# 09_-_mPCIE.net
KiCad netlist of a schematic drawn in Altium Designer
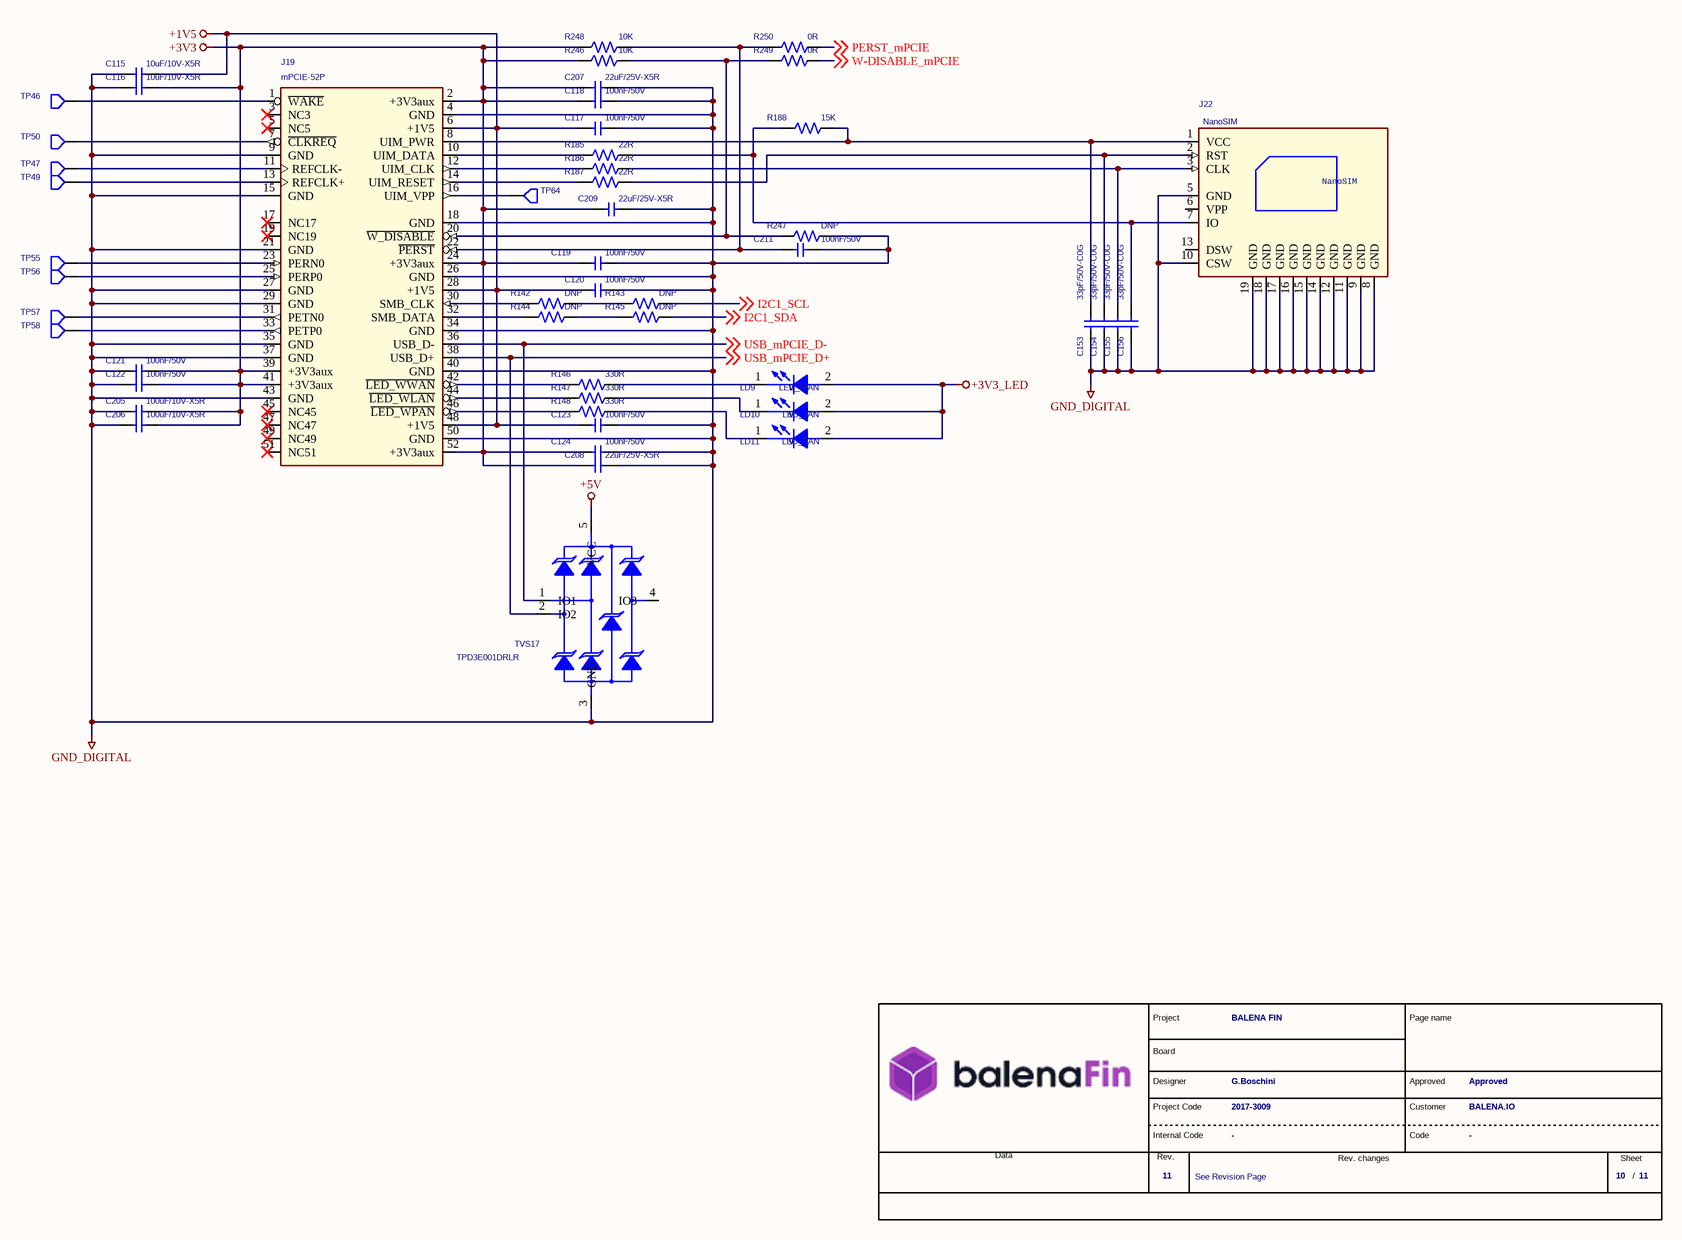
[diagram p0: 09 - mPCIE.SchDoc]

(export (version "E")
  (design (tool "Eeschema 10.0.6"))
  (components
    (comp (ref "C115")
      (value "10uF/10V-X5R")
      (footprint "CS-C-0603")
      (description "CHIP CAP.CER. 10uF 10V 10% X5R 0603")
      (fields (field (name "MPN") "Generic"))
      (libsource (lib "*") (part "CS-C-0603-10u/10V-X5R"))
    )
    (comp (ref "C116")
      (value "10uF/10V-X5R")
      (footprint "CS-C-0603")
      (description "CHIP CAP.CER. 10uF 10V 10% X5R 0603")
      (fields (field (name "MPN") "Generic"))
      (libsource (lib "*") (part "CS-C-0603-10u/10V-X5R"))
    )
    (comp (ref "C117")
      (value "100nF/50V")
      (footprint "CS-C-0402")
      (description "CHIP CAP.CER. 100nF 16V 10% X7R 0402")
      (fields (field (name "MPN") "Generic"))
      (libsource (lib "*") (part "CS-C-0402-100n/16V"))
    )
    (comp (ref "C118")
      (value "100nF/50V")
      (footprint "CS-C-0402")
      (description "CHIP CAP.CER. 100nF 16V 10% X7R 0402")
      (fields (field (name "MPN") "Generic"))
      (libsource (lib "*") (part "CS-C-0402-100n/16V"))
    )
    (comp (ref "C119")
      (value "100nF/50V")
      (footprint "CS-C-0402")
      (description "CHIP CAP.CER. 100nF 16V 10% X7R 0402")
      (fields (field (name "MPN") "Generic"))
      (libsource (lib "*") (part "CS-C-0402-100n/16V"))
    )
    (comp (ref "C120")
      (value "100nF/50V")
      (footprint "CS-C-0402")
      (description "CHIP CAP.CER. 100nF 16V 10% X7R 0402")
      (fields (field (name "MPN") "Generic"))
      (libsource (lib "*") (part "CS-C-0402-100n/16V"))
    )
    (comp (ref "C121")
      (value "100nF/50V")
      (footprint "CS-C-0402")
      (description "CHIP CAP.CER. 100nF 16V 10% X7R 0402")
      (fields (field (name "MPN") "Generic"))
      (libsource (lib "*") (part "CS-C-0402-100n/16V"))
    )
    (comp (ref "C122")
      (value "100nF/50V")
      (footprint "CS-C-0402")
      (description "CHIP CAP.CER. 100nF 16V 10% X7R 0402")
      (fields (field (name "MPN") "Generic"))
      (libsource (lib "*") (part "CS-C-0402-100n/16V"))
    )
    (comp (ref "C123")
      (value "100nF/50V")
      (footprint "CS-C-0402")
      (description "CHIP CAP.CER. 100nF 16V 10% X7R 0402")
      (fields (field (name "MPN") "Generic"))
      (libsource (lib "*") (part "CS-C-0402-100n/16V"))
    )
    (comp (ref "C124")
      (value "100nF/50V")
      (footprint "CS-C-0402")
      (description "CHIP CAP.CER. 100nF 16V 10% X7R 0402")
      (fields (field (name "MPN") "Generic"))
      (libsource (lib "*") (part "CS-C-0402-100n/16V"))
    )
    (comp (ref "C153")
      (value "33pF/50V-C0G")
      (footprint "CS-C-0402")
      (description "CHIP CAP.CER. 33pF 50V 5% C0G 0402")
      (fields (field (name "MPN") "Generic"))
      (libsource (lib "*") (part "CS-C-0402-33p/50V-C0G"))
    )
    (comp (ref "C154")
      (value "33pF/50V-C0G")
      (footprint "CS-C-0402")
      (description "CHIP CAP.CER. 33pF 50V 5% C0G 0402")
      (fields (field (name "MPN") "Generic"))
      (libsource (lib "*") (part "CS-C-0402-33p/50V-C0G"))
    )
    (comp (ref "C155")
      (value "33pF/50V-C0G")
      (footprint "CS-C-0402")
      (description "CHIP CAP.CER. 33pF 50V 5% C0G 0402")
      (fields (field (name "MPN") "Generic"))
      (libsource (lib "*") (part "CS-C-0402-33p/50V-C0G"))
    )
    (comp (ref "C156")
      (value "33pF/50V-C0G")
      (footprint "CS-C-0402")
      (description "CHIP CAP.CER. 33pF 50V 5% C0G 0402")
      (fields (field (name "MPN") "Generic"))
      (libsource (lib "*") (part "CS-C-0402-33p/50V-C0G"))
    )
    (comp (ref "C205")
      (value "100uF/10V-X5R")
      (footprint "CS-C-1210")
      (description "CHIP CAP.CER. 100UF 10V 20% X5R 1210")
      (fields (field (name "MPN") "Generic"))
      (libsource (lib "*") (part "CS-C-1210-100u/10V-X5R"))
    )
    (comp (ref "C206")
      (value "100uF/10V-X5R")
      (footprint "CS-C-1210")
      (description "CHIP CAP.CER. 100UF 10V 20% X5R 1210")
      (fields (field (name "MPN") "Generic"))
      (libsource (lib "*") (part "CS-C-1210-100u/10V-X5R"))
    )
    (comp (ref "C207")
      (value "22uF/25V-X5R")
      (footprint "CS-C-1206")
      (description "CHIP CAP.CER. 22uF 25V 10% X5R 1206")
      (fields (field (name "MPN") "Generic"))
      (libsource (lib "*") (part "CS-C-1206-22u/25V-X5R"))
    )
    (comp (ref "C208")
      (value "22uF/25V-X5R")
      (footprint "CS-C-1206")
      (description "CHIP CAP.CER. 22uF 25V 10% X5R 1206")
      (fields (field (name "MPN") "Generic"))
      (libsource (lib "*") (part "CS-C-1206-22u/25V-X5R"))
    )
    (comp (ref "C209")
      (value "22uF/25V-X5R")
      (footprint "CS-C-1206")
      (description "CHIP CAP.CER. 22uF 25V 10% X5R 1206")
      (fields (field (name "MPN") "Generic"))
      (libsource (lib "*") (part "CS-C-1206-22u/25V-X5R"))
    )
    (comp (ref "C211")
      (value "100nF/50V")
      (footprint "CS-C-0402")
      (description "CHIP CAP.CER. 100nF 16V 10% X7R 0402")
      (fields (field (name "MPN") "Generic"))
      (libsource (lib "*") (part "CS-C-0402-100n/16V"))
    )
    (comp (ref "J19")
      (value "mPCIE-52P")
      (footprint "J-26X2-0080-FOS-2041119")
      (description "CONN PCI EXP MINI FEMALE 52POS")
      (fields (field (name "MPN") "2041119-1"))
      (libsource (lib "*") (part "mPCIE - J-26X2-0080-FOS-2041119"))
    )
    (comp (ref "J22")
      (value "NanoSIM")
      (footprint "J-NANOSIM-SF72S006VBA")
      (description "CONN NANO SIM CARD PUSH-PUSH")
      (fields (field (name "MPN") "SF72S006VBAR2500"))
      (libsource (lib "*") (part "NANOSIM - J-NANOSIM-SF72S006VBA"))
    )
    (comp (ref "LD9")
      (value "LED_WAN")
      (footprint "LD-0603")
      (description "LED Green 0603 SMT")
      (fields (field (name "MPN") "Generic"))
      (libsource (lib "*") (part "LED V - GENERICO - 0603"))
    )
    (comp (ref "LD10")
      (value "LED_LAN")
      (footprint "LD-0603")
      (description "LED Green 0603 SMT")
      (fields (field (name "MPN") "Generic"))
      (libsource (lib "*") (part "LED V - GENERICO - 0603"))
    )
    (comp (ref "LD11")
      (value "LED_PAN")
      (footprint "LD-0603")
      (description "LED Green 0603 SMT")
      (fields (field (name "MPN") "Generic"))
      (libsource (lib "*") (part "LED V - GENERICO - 0603"))
    )
    (comp (ref "R142")
      (value "DNP")
      (footprint "RS-0402")
      (description "CHIP RES. 0402")
      (fields (field (name "MPN") "Generic"))
      (libsource (lib "*") (part "RS-0402"))
    )
    (comp (ref "R143")
      (value "DNP")
      (footprint "RS-0402")
      (description "CHIP RES. 0402")
      (fields (field (name "MPN") "Generic"))
      (libsource (lib "*") (part "RS-0402"))
    )
    (comp (ref "R144")
      (value "DNP")
      (footprint "RS-0402")
      (description "CHIP RES. 0402")
      (fields (field (name "MPN") "Generic"))
      (libsource (lib "*") (part "RS-0402"))
    )
    (comp (ref "R145")
      (value "DNP")
      (footprint "RS-0402")
      (description "CHIP RES. 0402")
      (fields (field (name "MPN") "Generic"))
      (libsource (lib "*") (part "RS-0402"))
    )
    (comp (ref "R146")
      (value "330R")
      (footprint "RS-0402")
      (description "CHIP RES. 330R 0402 1/16W 1%")
      (fields (field (name "MPN") "Generic"))
      (libsource (lib "*") (part "RS-0402-330r"))
    )
    (comp (ref "R147")
      (value "330R")
      (footprint "RS-0402")
      (description "CHIP RES. 330R 0402 1/16W 1%")
      (fields (field (name "MPN") "Generic"))
      (libsource (lib "*") (part "RS-0402-330r"))
    )
    (comp (ref "R148")
      (value "330R")
      (footprint "RS-0402")
      (description "CHIP RES. 330R 0402 1/16W 1%")
      (fields (field (name "MPN") "Generic"))
      (libsource (lib "*") (part "RS-0402-330r"))
    )
    (comp (ref "R185")
      (value "22R")
      (footprint "RS-0603")
      (description "CHIP RES. 22R 0603 1/16W 1%")
      (fields (field (name "MPN") "Generic"))
      (libsource (lib "*") (part "RS-0603-22r"))
    )
    (comp (ref "R186")
      (value "22R")
      (footprint "RS-0603")
      (description "CHIP RES. 22R 0603 1/16W 1%")
      (fields (field (name "MPN") "Generic"))
      (libsource (lib "*") (part "RS-0603-22r"))
    )
    (comp (ref "R187")
      (value "22R")
      (footprint "RS-0603")
      (description "CHIP RES. 22R 0603 1/16W 1%")
      (fields (field (name "MPN") "Generic"))
      (libsource (lib "*") (part "RS-0603-22r"))
    )
    (comp (ref "R188")
      (value "15K")
      (footprint "RS-0402")
      (description "CHIP RES. 15K 0402 1/16W 1%")
      (fields (field (name "MPN") "Generic"))
      (libsource (lib "*") (part "RS-0402-15k"))
    )
    (comp (ref "R246")
      (value "10K")
      (footprint "RS-0402")
      (description "CHIP RES. 10K 0402 1/16W 1%")
      (fields (field (name "MPN") "Generic"))
      (libsource (lib "*") (part "RS-0402-10k"))
    )
    (comp (ref "R247")
      (value "DNP")
      (footprint "RS-0402")
      (description "CHIP RES. 0402")
      (fields (field (name "MPN") "Generic"))
      (libsource (lib "*") (part "RS-0402"))
    )
    (comp (ref "R248")
      (value "10K")
      (footprint "RS-0402")
      (description "CHIP RES. 10K 0402 1/16W 1%")
      (fields (field (name "MPN") "Generic"))
      (libsource (lib "*") (part "RS-0402-10k"))
    )
    (comp (ref "R249")
      (value "0R")
      (footprint "RS-0402")
      (description "CHIP RES. 0R 0402 1/16W 1%")
      (fields (field (name "MPN") "Generic"))
      (libsource (lib "*") (part "RS-0402-0r"))
    )
    (comp (ref "R250")
      (value "0R")
      (footprint "RS-0402")
      (description "CHIP RES. 0R 0402 1/16W 1%")
      (fields (field (name "MPN") "Generic"))
      (libsource (lib "*") (part "RS-0402-0r"))
    )
    (comp (ref "TP46")
      (value "TPS")
      (footprint "TPS-0100")
      (description "TEST POINT SMD")
      (fields (field (name "MPN") "TP-No-BoM"))
      (libsource (lib "*") (part "TEST POINT SMD 1 MM"))
    )
    (comp (ref "TP47")
      (value "TPS")
      (footprint "TPS-0100")
      (description "TEST POINT SMD")
      (fields (field (name "MPN") "TP-No-BoM"))
      (libsource (lib "*") (part "TEST POINT SMD 1 MM"))
    )
    (comp (ref "TP49")
      (value "TPS")
      (footprint "TPS-0100")
      (description "TEST POINT SMD")
      (fields (field (name "MPN") "TP-No-BoM"))
      (libsource (lib "*") (part "TEST POINT SMD 1 MM"))
    )
    (comp (ref "TP50")
      (value "TPS")
      (footprint "TPS-0100")
      (description "TEST POINT SMD")
      (fields (field (name "MPN") "TP-No-BoM"))
      (libsource (lib "*") (part "TEST POINT SMD 1 MM"))
    )
    (comp (ref "TP55")
      (value "TPS")
      (footprint "TPS-0100")
      (description "TEST POINT SMD")
      (fields (field (name "MPN") "TP-No-BoM"))
      (libsource (lib "*") (part "TEST POINT SMD 1 MM"))
    )
    (comp (ref "TP56")
      (value "TPS")
      (footprint "TPS-0100")
      (description "TEST POINT SMD")
      (fields (field (name "MPN") "TP-No-BoM"))
      (libsource (lib "*") (part "TEST POINT SMD 1 MM"))
    )
    (comp (ref "TP57")
      (value "TPS")
      (footprint "TPS-0100")
      (description "TEST POINT SMD")
      (fields (field (name "MPN") "TP-No-BoM"))
      (libsource (lib "*") (part "TEST POINT SMD 1 MM"))
    )
    (comp (ref "TP58")
      (value "TPS")
      (footprint "TPS-0100")
      (description "TEST POINT SMD")
      (fields (field (name "MPN") "TP-No-BoM"))
      (libsource (lib "*") (part "TEST POINT SMD 1 MM"))
    )
    (comp (ref "TP64")
      (value "TPS")
      (footprint "TPS-0100")
      (description "TEST POINT SMD")
      (fields (field (name "MPN") "TP-No-BoM"))
      (libsource (lib "*") (part "TEST POINT SMD 1 MM"))
    )
    (comp (ref "TVS17")
      (value "TPD3E001DRLR")
      (footprint "SOP5_USON6")
      (description "TVS DIODE 5.5VWM")
      (libsource (lib "*") (part "TVS-UNI3x - TPD3E001DRLR - USB"))
    )
  )
  (nets
    (net (code "1") (name "+1V5") (class "Default")
      (node (ref "C115") (pin "2") (pinfunction "2_2") (pintype "passive"))
      (node (ref "C117") (pin "1") (pinfunction "1_1") (pintype "passive"))
      (node (ref "C120") (pin "1") (pinfunction "1_1") (pintype "passive"))
      (node (ref "C123") (pin "1") (pinfunction "1_1") (pintype "passive"))
      (node (ref "J19") (pin "28") (pinfunction "+1V5_28") (pintype "power_in"))
      (node (ref "J19") (pin "48") (pinfunction "+1V5_48") (pintype "power_in"))
      (node (ref "J19") (pin "6") (pinfunction "+1V5_6") (pintype "power_in"))
    )
    (net (code "2") (name "+3V3") (class "Default")
      (node (ref "C116") (pin "2") (pinfunction "2_2") (pintype "passive"))
      (node (ref "C118") (pin "1") (pinfunction "1_1") (pintype "passive"))
      (node (ref "C119") (pin "1") (pinfunction "1_1") (pintype "passive"))
      (node (ref "C121") (pin "2") (pinfunction "2_2") (pintype "passive"))
      (node (ref "C122") (pin "2") (pinfunction "2_2") (pintype "passive"))
      (node (ref "C124") (pin "1") (pinfunction "1_1") (pintype "passive"))
      (node (ref "C205") (pin "2") (pinfunction "2_2") (pintype "passive"))
      (node (ref "C206") (pin "2") (pinfunction "2_2") (pintype "passive"))
      (node (ref "C207") (pin "1") (pinfunction "1_1") (pintype "passive"))
      (node (ref "C208") (pin "1") (pinfunction "1_1") (pintype "passive"))
      (node (ref "C209") (pin "1") (pinfunction "1_1") (pintype "passive"))
      (node (ref "J19") (pin "2") (pinfunction "+3V3aux_2") (pintype "power_in"))
      (node (ref "J19") (pin "24") (pinfunction "+3V3aux_24") (pintype "power_in"))
      (node (ref "J19") (pin "39") (pinfunction "+3V3aux_39") (pintype "power_in"))
      (node (ref "J19") (pin "41") (pinfunction "+3V3aux_41") (pintype "power_in"))
      (node (ref "J19") (pin "52") (pinfunction "+3V3aux_52") (pintype "power_in"))
      (node (ref "R246") (pin "2") (pinfunction "2_2") (pintype "passive"))
      (node (ref "R248") (pin "2") (pinfunction "2_2") (pintype "passive"))
    )
    (net (code "3") (name "+3V3_LED") (class "Default")
      (node (ref "LD10") (pin "2") (pinfunction "A_2") (pintype "passive"))
      (node (ref "LD11") (pin "2") (pinfunction "A_2") (pintype "passive"))
      (node (ref "LD9") (pin "2") (pinfunction "A_2") (pintype "passive"))
    )
    (net (code "4") (name "+5V") (class "Default")
      (node (ref "TVS17") (pin "5") (pinfunction "VCC_5") (pintype "passive"))
    )
    (net (code "5") (name "GND_DIGITAL") (class "Default")
      (node (ref "C115") (pin "1") (pinfunction "1_1") (pintype "passive"))
      (node (ref "C116") (pin "1") (pinfunction "1_1") (pintype "passive"))
      (node (ref "C117") (pin "2") (pinfunction "2_2") (pintype "passive"))
      (node (ref "C118") (pin "2") (pinfunction "2_2") (pintype "passive"))
      (node (ref "C119") (pin "2") (pinfunction "2_2") (pintype "passive"))
      (node (ref "C120") (pin "2") (pinfunction "2_2") (pintype "passive"))
      (node (ref "C121") (pin "1") (pinfunction "1_1") (pintype "passive"))
      (node (ref "C122") (pin "1") (pinfunction "1_1") (pintype "passive"))
      (node (ref "C123") (pin "2") (pinfunction "2_2") (pintype "passive"))
      (node (ref "C124") (pin "2") (pinfunction "2_2") (pintype "passive"))
      (node (ref "C153") (pin "2") (pinfunction "2_2") (pintype "passive"))
      (node (ref "C154") (pin "2") (pinfunction "2_2") (pintype "passive"))
      (node (ref "C155") (pin "2") (pinfunction "2_2") (pintype "passive"))
      (node (ref "C156") (pin "2") (pinfunction "2_2") (pintype "passive"))
      (node (ref "C205") (pin "1") (pinfunction "1_1") (pintype "passive"))
      (node (ref "C206") (pin "1") (pinfunction "1_1") (pintype "passive"))
      (node (ref "C207") (pin "2") (pinfunction "2_2") (pintype "passive"))
      (node (ref "C208") (pin "2") (pinfunction "2_2") (pintype "passive"))
      (node (ref "C209") (pin "2") (pinfunction "2_2") (pintype "passive"))
      (node (ref "C211") (pin "2") (pinfunction "2_2") (pintype "passive"))
      (node (ref "J19") (pin "15") (pinfunction "GND_15") (pintype "power_in"))
      (node (ref "J19") (pin "18") (pinfunction "GND_18") (pintype "power_in"))
      (node (ref "J19") (pin "21") (pinfunction "GND_21") (pintype "power_in"))
      (node (ref "J19") (pin "26") (pinfunction "GND_26") (pintype "power_in"))
      (node (ref "J19") (pin "27") (pinfunction "GND_27") (pintype "power_in"))
      (node (ref "J19") (pin "29") (pinfunction "GND_29") (pintype "power_in"))
      (node (ref "J19") (pin "34") (pinfunction "GND_34") (pintype "power_in"))
      (node (ref "J19") (pin "35") (pinfunction "GND_35") (pintype "power_in"))
      (node (ref "J19") (pin "37") (pinfunction "GND_37") (pintype "power_in"))
      (node (ref "J19") (pin "4") (pinfunction "GND_4") (pintype "power_in"))
      (node (ref "J19") (pin "40") (pinfunction "GND_40") (pintype "power_in"))
      (node (ref "J19") (pin "43") (pinfunction "GND_43") (pintype "power_in"))
      (node (ref "J19") (pin "50") (pinfunction "GND_50") (pintype "power_in"))
      (node (ref "J19") (pin "9") (pinfunction "GND_9") (pintype "power_in"))
      (node (ref "J22") (pin "10") (pinfunction "CSW_10") (pintype "passive"))
      (node (ref "J22") (pin "11") (pinfunction "GND_11") (pintype "power_in"))
      (node (ref "J22") (pin "12") (pinfunction "GND_12") (pintype "power_in"))
      (node (ref "J22") (pin "14") (pinfunction "GND_14") (pintype "power_in"))
      (node (ref "J22") (pin "15") (pinfunction "GND_15") (pintype "power_in"))
      (node (ref "J22") (pin "16") (pinfunction "GND_16") (pintype "power_in"))
      (node (ref "J22") (pin "17") (pinfunction "GND_17") (pintype "power_in"))
      (node (ref "J22") (pin "18") (pinfunction "GND_18") (pintype "power_in"))
      (node (ref "J22") (pin "19") (pinfunction "GND_19") (pintype "power_in"))
      (node (ref "J22") (pin "5") (pinfunction "GND_5") (pintype "power_in"))
      (node (ref "J22") (pin "8") (pinfunction "GND_8") (pintype "power_in"))
      (node (ref "J22") (pin "9") (pinfunction "GND_9") (pintype "power_in"))
      (node (ref "R247") (pin "1") (pinfunction "1_1") (pintype "passive"))
      (node (ref "TVS17") (pin "3") (pinfunction "GND_3") (pintype "power_in"))
    )
    (net (code "6") (name "I2C1_SCL") (class "Default")
      (node (ref "R143") (pin "2") (pinfunction "2_2") (pintype "passive"))
    )
    (net (code "7") (name "I2C1_SDA") (class "Default")
      (node (ref "R145") (pin "2") (pinfunction "2_2") (pintype "passive"))
    )
    (net (code "8") (name "Net-(J19-PERN0)") (class "Default")
      (node (ref "J19") (pin "23") (pinfunction "PERN0_23") (pintype "input"))
      (node (ref "TP55") (pin "1") (pinfunction "TP_1") (pintype "passive"))
    )
    (net (code "9") (name "Net-(J19-PERP0)") (class "Default")
      (node (ref "J19") (pin "25") (pinfunction "PERP0_25") (pintype "input"))
      (node (ref "TP56") (pin "1") (pinfunction "TP_1") (pintype "passive"))
    )
    (net (code "10") (name "Net-(J19-PETN0)") (class "Default")
      (node (ref "J19") (pin "31") (pinfunction "PETN0_31") (pintype "output"))
      (node (ref "TP57") (pin "1") (pinfunction "TP_1") (pintype "passive"))
    )
    (net (code "11") (name "Net-(J19-PETP0)") (class "Default")
      (node (ref "J19") (pin "33") (pinfunction "PETP0_33") (pintype "output"))
      (node (ref "TP58") (pin "1") (pinfunction "TP_1") (pintype "passive"))
    )
    (net (code "12") (name "Net-(J19-REFCLK+)") (class "Default")
      (node (ref "J19") (pin "13") (pinfunction "REFCLK+_13") (pintype "bidirectional"))
      (node (ref "TP49") (pin "1") (pinfunction "TP_1") (pintype "passive"))
    )
    (net (code "13") (name "Net-(J19-REFCLK-)") (class "Default")
      (node (ref "J19") (pin "11") (pinfunction "REFCLK-_11") (pintype "bidirectional"))
      (node (ref "TP47") (pin "1") (pinfunction "TP_1") (pintype "passive"))
    )
    (net (code "14") (name "Net-(J19-SMB_CLK)") (class "Default")
      (node (ref "J19") (pin "30") (pinfunction "SMB_CLK_30") (pintype "input"))
      (node (ref "R142") (pin "1") (pinfunction "1_1") (pintype "passive"))
    )
    (net (code "15") (name "Net-(J19-SMB_DATA)") (class "Default")
      (node (ref "J19") (pin "32") (pinfunction "SMB_DATA_32") (pintype "bidirectional"))
      (node (ref "R144") (pin "1") (pinfunction "1_1") (pintype "passive"))
    )
    (net (code "16") (name "Net-(J19-UIM_CLK)") (class "Default")
      (node (ref "J19") (pin "12") (pinfunction "UIM_CLK_12") (pintype "output"))
      (node (ref "R186") (pin "1") (pinfunction "1_1") (pintype "passive"))
    )
    (net (code "17") (name "Net-(J19-UIM_DATA)") (class "Default")
      (node (ref "J19") (pin "10") (pinfunction "UIM_DATA_10") (pintype "bidirectional"))
      (node (ref "R185") (pin "1") (pinfunction "1_1") (pintype "passive"))
    )
    (net (code "18") (name "Net-(J19-UIM_PWR)") (class "Default")
      (node (ref "C153") (pin "1") (pinfunction "1_1") (pintype "passive"))
      (node (ref "J19") (pin "8") (pinfunction "UIM_PWR_8") (pintype "power_in"))
      (node (ref "J22") (pin "1") (pinfunction "VCC_1") (pintype "power_in"))
      (node (ref "R188") (pin "2") (pinfunction "2_2") (pintype "passive"))
    )
    (net (code "19") (name "Net-(J19-UIM_RESET)") (class "Default")
      (node (ref "J19") (pin "14") (pinfunction "UIM_RESET_14") (pintype "output"))
      (node (ref "R187") (pin "1") (pinfunction "1_1") (pintype "passive"))
    )
    (net (code "20") (name "Net-(J19-UIM_VPP)") (class "Default")
      (node (ref "J19") (pin "16") (pinfunction "UIM_VPP_16") (pintype "output"))
      (node (ref "TP64") (pin "1") (pinfunction "TP_1") (pintype "passive"))
    )
    (net (code "21") (name "Net-(J19-~{CLKREQ})") (class "Default")
      (node (ref "J19") (pin "7") (pinfunction "~{CLKREQ}_7") (pintype "output"))
      (node (ref "TP50") (pin "1") (pinfunction "TP_1") (pintype "passive"))
    )
    (net (code "22") (name "Net-(J19-~{LED_WLAN})") (class "Default")
      (node (ref "J19") (pin "44") (pinfunction "~{LED_WLAN}_44") (pintype "output"))
      (node (ref "R147") (pin "1") (pinfunction "1_1") (pintype "passive"))
    )
    (net (code "23") (name "Net-(J19-~{LED_WPAN})") (class "Default")
      (node (ref "J19") (pin "46") (pinfunction "~{LED_WPAN}_46") (pintype "output"))
      (node (ref "R148") (pin "1") (pinfunction "1_1") (pintype "passive"))
    )
    (net (code "24") (name "Net-(J19-~{LED_WWAN})") (class "Default")
      (node (ref "J19") (pin "42") (pinfunction "~{LED_WWAN}_42") (pintype "output"))
      (node (ref "R146") (pin "1") (pinfunction "1_1") (pintype "passive"))
    )
    (net (code "25") (name "Net-(J19-~{PERST})") (class "Default")
      (node (ref "C211") (pin "1") (pinfunction "1_1") (pintype "passive"))
      (node (ref "J19") (pin "22") (pinfunction "~{PERST}_22") (pintype "input"))
      (node (ref "R248") (pin "1") (pinfunction "1_1") (pintype "passive"))
      (node (ref "R250") (pin "1") (pinfunction "1_1") (pintype "passive"))
    )
    (net (code "26") (name "Net-(J19-~{WAKE})") (class "Default")
      (node (ref "J19") (pin "1") (pinfunction "~{WAKE}_1") (pintype "passive"))
      (node (ref "TP46") (pin "1") (pinfunction "TP_1") (pintype "passive"))
    )
    (net (code "27") (name "Net-(J19-~{W_DISABLE})") (class "Default")
      (node (ref "J19") (pin "20") (pinfunction "~{W_DISABLE}_20") (pintype "input"))
      (node (ref "R246") (pin "1") (pinfunction "1_1") (pintype "passive"))
      (node (ref "R247") (pin "2") (pinfunction "2_2") (pintype "passive"))
      (node (ref "R249") (pin "1") (pinfunction "1_1") (pintype "passive"))
    )
    (net (code "28") (name "Net-(J22-CLK)") (class "Default")
      (node (ref "C155") (pin "1") (pinfunction "1_1") (pintype "passive"))
      (node (ref "J22") (pin "3") (pinfunction "CLK_3") (pintype "input"))
      (node (ref "R186") (pin "2") (pinfunction "2_2") (pintype "passive"))
    )
    (net (code "29") (name "Net-(J22-IO)") (class "Default")
      (node (ref "C156") (pin "1") (pinfunction "1_1") (pintype "passive"))
      (node (ref "J22") (pin "7") (pinfunction "IO_7") (pintype "bidirectional"))
      (node (ref "R185") (pin "2") (pinfunction "2_2") (pintype "passive"))
      (node (ref "R188") (pin "1") (pinfunction "1_1") (pintype "passive"))
    )
    (net (code "30") (name "Net-(J22-RST)") (class "Default")
      (node (ref "C154") (pin "1") (pinfunction "1_1") (pintype "passive"))
      (node (ref "J22") (pin "2") (pinfunction "RST_2") (pintype "input"))
      (node (ref "R187") (pin "2") (pinfunction "2_2") (pintype "passive"))
    )
    (net (code "31") (name "Net-(LD9-C)") (class "Default")
      (node (ref "LD9") (pin "1") (pinfunction "C_1") (pintype "passive"))
      (node (ref "R146") (pin "2") (pinfunction "2_2") (pintype "passive"))
    )
    (net (code "32") (name "Net-(LD10-C)") (class "Default")
      (node (ref "LD10") (pin "1") (pinfunction "C_1") (pintype "passive"))
      (node (ref "R147") (pin "2") (pinfunction "2_2") (pintype "passive"))
    )
    (net (code "33") (name "Net-(LD11-C)") (class "Default")
      (node (ref "LD11") (pin "1") (pinfunction "C_1") (pintype "passive"))
      (node (ref "R148") (pin "2") (pinfunction "2_2") (pintype "passive"))
    )
    (net (code "34") (name "Net-(R142-Pad2)") (class "Default")
      (node (ref "R142") (pin "2") (pinfunction "2_2") (pintype "passive"))
      (node (ref "R143") (pin "1") (pinfunction "1_1") (pintype "passive"))
    )
    (net (code "35") (name "Net-(R144-Pad2)") (class "Default")
      (node (ref "R144") (pin "2") (pinfunction "2_2") (pintype "passive"))
      (node (ref "R145") (pin "1") (pinfunction "1_1") (pintype "passive"))
    )
    (net (code "36") (name "PERST_mPCIE") (class "Default")
      (node (ref "R250") (pin "2") (pinfunction "2_2") (pintype "passive"))
    )
    (net (code "37") (name "USB_mPCIE_D+") (class "Default")
      (node (ref "J19") (pin "38") (pinfunction "USB_D+_38") (pintype "bidirectional"))
      (node (ref "TVS17") (pin "2") (pinfunction "IO2_2") (pintype "passive"))
    )
    (net (code "38") (name "USB_mPCIE_D-") (class "Default")
      (node (ref "J19") (pin "36") (pinfunction "USB_D-_36") (pintype "bidirectional"))
      (node (ref "TVS17") (pin "1") (pinfunction "IO1_1") (pintype "passive"))
    )
    (net (code "39") (name "W-DISABLE_mPCIE") (class "Default")
      (node (ref "R249") (pin "2") (pinfunction "2_2") (pintype "passive"))
    )
    (net (code "40") (name "unconnected-(J19-NC3-Pad3)") (class "Default")
      (node (ref "J19") (pin "3") (pinfunction "NC3_3") (pintype "passive+no_connect"))
    )
    (net (code "41") (name "unconnected-(J19-NC5-Pad5)") (class "Default")
      (node (ref "J19") (pin "5") (pinfunction "NC5_5") (pintype "passive+no_connect"))
    )
    (net (code "42") (name "unconnected-(J19-NC17-Pad17)") (class "Default")
      (node (ref "J19") (pin "17") (pinfunction "NC17_17") (pintype "passive+no_connect"))
    )
    (net (code "43") (name "unconnected-(J19-NC19-Pad19)") (class "Default")
      (node (ref "J19") (pin "19") (pinfunction "NC19_19") (pintype "passive+no_connect"))
    )
    (net (code "44") (name "unconnected-(J19-NC45-Pad45)") (class "Default")
      (node (ref "J19") (pin "45") (pinfunction "NC45_45") (pintype "passive+no_connect"))
    )
    (net (code "45") (name "unconnected-(J19-NC47-Pad47)") (class "Default")
      (node (ref "J19") (pin "47") (pinfunction "NC47_47") (pintype "passive+no_connect"))
    )
    (net (code "46") (name "unconnected-(J19-NC49-Pad49)") (class "Default")
      (node (ref "J19") (pin "49") (pinfunction "NC49_49") (pintype "passive+no_connect"))
    )
    (net (code "47") (name "unconnected-(J19-NC51-Pad51)") (class "Default")
      (node (ref "J19") (pin "51") (pinfunction "NC51_51") (pintype "passive+no_connect"))
    )
    (net (code "48") (name "unconnected-(J22-DSW-Pad13)") (class "Default")
      (node (ref "J22") (pin "13") (pinfunction "DSW_13") (pintype "passive"))
    )
    (net (code "49") (name "unconnected-(J22-VPP-Pad6)") (class "Default")
      (node (ref "J22") (pin "6") (pinfunction "VPP_6") (pintype "passive"))
    )
    (net (code "50") (name "unconnected-(TVS17-IO3-Pad4)") (class "Default")
      (node (ref "TVS17") (pin "4") (pinfunction "IO3_4") (pintype "passive"))
    )
  )
)
